# ProPrj_Lan_Relay_blog_2026-03-05_10-33-5.net
KiCad netlist of a schematic drawn in EasyEDA Pro
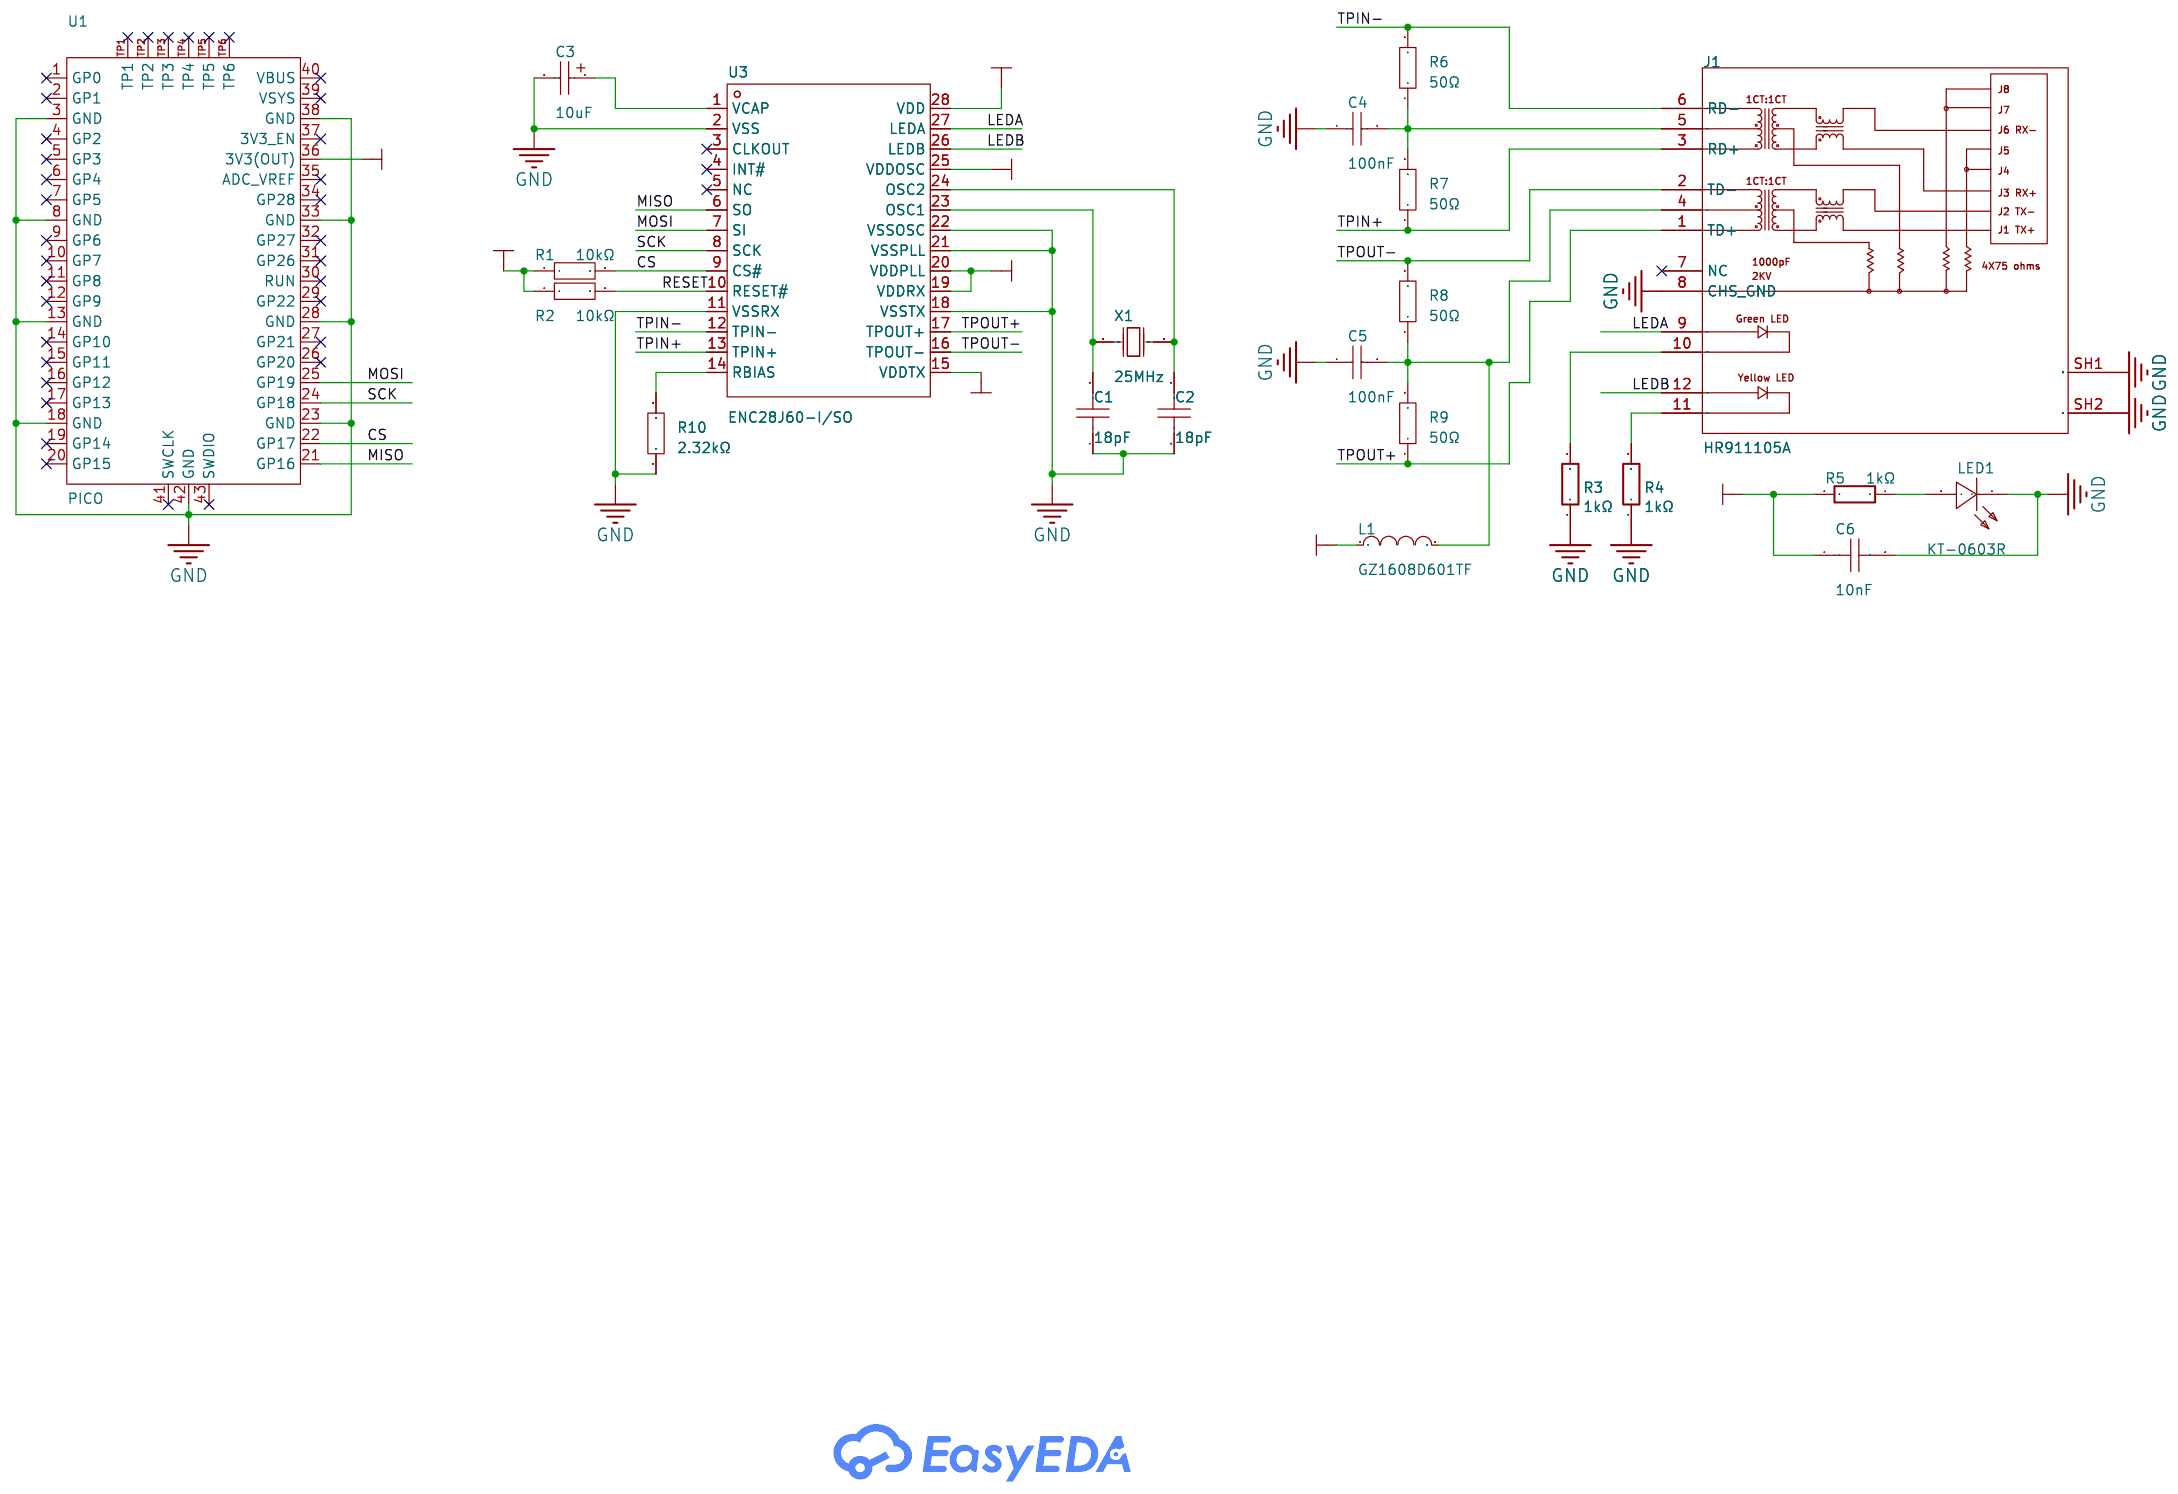
[diagram p0: schematic sheet]

(export (version "E")
  (design (tool "Eeschema 10.0.6"))
  (components
    (comp (ref "C1")
      (value "18pF")
      (description "Capacitance:18pF Tolerance:±5% Tolerance:±5% Voltage Rating:50V Temperature Coefficient:C0G")
      (fields
        (field (name "Manufacturer Part") "CL10C180JB8NNNC")
        (field (name "Manufacturer") "SAMSUNG(三星)")
      )
      (libsource (lib "easyedapro") (part "CAP"))
    )
    (comp (ref "C2")
      (value "18pF")
      (description "Capacitance:18pF Tolerance:±5% Tolerance:±5% Voltage Rating:50V Temperature Coefficient:C0G")
      (fields
        (field (name "Manufacturer Part") "CL10C180JB8NNNC")
        (field (name "Manufacturer") "SAMSUNG(三星)")
      )
      (libsource (lib "easyedapro") (part "CAP"))
    )
    (comp (ref "C3")
      (value "10uF")
      (footprint "easyedapro:CAP-SMD_L3.2-W1.6-RD-C7171")
      (fields (field (name "Manufacturer Part") "TAJA106K016RNJ") (field (name "Manufacturer") "Kyocera AVX"))
      (libsource (lib "easyedapro") (part "TAJA106K016RNJ"))
    )
    (comp (ref "C4")
      (value "100nF")
      (footprint "easyedapro:C0805")
      (description "Capacitance:100nF Tolerance:±10% Tolerance:±10% Voltage Rating:100V Temperature Coefficient:X7R")
      (fields
        (field (name "Manufacturer Part") "CL21B104KCFNNNE")
        (field (name "Manufacturer") "SAMSUNG(三星)")
      )
      (libsource (lib "easyedapro") (part "CL21B104KCFNNNE"))
    )
    (comp (ref "C5")
      (value "100nF")
      (footprint "easyedapro:C0805")
      (description "Capacitance:100nF Tolerance:±10% Tolerance:±10% Voltage Rating:100V Temperature Coefficient:X7R")
      (fields
        (field (name "Manufacturer Part") "CL21B104KCFNNNE")
        (field (name "Manufacturer") "SAMSUNG(三星)")
      )
      (libsource (lib "easyedapro") (part "CL21B104KCFNNNE"))
    )
    (comp (ref "C6")
      (value "10nF")
      (description "Capacitance:10nF Tolerance:±10% Tolerance:±10% Voltage Rating:50V Temperature Coefficient:X7R")
      (fields (field (name "Manufacturer Part") "0603B103K500NT") (field (name "Manufacturer") "FH(风华)"))
      (libsource (lib "easyedapro") (part "CAP"))
    )
    (comp (ref "J1")
      (value "HR911105A")
      (footprint "easyedapro:RJ45-TH_HR911105A")
      (fields (field (name "Manufacturer") "HANRUN(汉仁)"))
      (libsource (lib "easyedapro") (part "HR911105A_C12074"))
    )
    (comp (ref "L1")
      (value "GZ1608D601TF")
      (footprint "easyedapro:L0603")
      (fields (field (name "Manufacturer") "Sunlord(顺络)"))
      (libsource (lib "easyedapro") (part "GZ1608D601TF"))
    )
    (comp (ref "LED1")
      (value "KT-0603R")
      (footprint "easyedapro:LED0603-RD")
      (fields (field (name "Manufacturer") "KENTO"))
      (libsource (lib "easyedapro") (part "KT-0603R"))
    )
    (comp (ref "R1")
      (value "10kΩ")
      (fields
        (field (name "Manufacturer Part") "0603WAF1002T5E")
        (field (name "Manufacturer") "UNI-ROYAL(厚声)")
      )
      (libsource (lib "easyedapro") (part "Res"))
    )
    (comp (ref "R2")
      (value "10kΩ")
      (fields
        (field (name "Manufacturer Part") "0603WAF1002T5E")
        (field (name "Manufacturer") "UNI-ROYAL(厚声)")
      )
      (libsource (lib "easyedapro") (part "Res"))
    )
    (comp (ref "R3")
      (value "1kΩ")
      (fields (field (name "Manufacturer") "UNI-ROYAL(厚声)"))
      (libsource (lib "easyedapro") (part "1k"))
    )
    (comp (ref "R4")
      (value "1kΩ")
      (fields (field (name "Manufacturer") "UNI-ROYAL(厚声)"))
      (libsource (lib "easyedapro") (part "1k"))
    )
    (comp (ref "R5")
      (value "1kΩ")
      (fields (field (name "Manufacturer") "UNI-ROYAL(厚声)"))
      (libsource (lib "easyedapro") (part "1k"))
    )
    (comp (ref "R6")
      (value "50Ω")
      (fields
        (field (name "Manufacturer Part") "CRCW060350R0FKEA")
        (field (name "Manufacturer") "VISHAY(威世)")
      )
      (libsource (lib "easyedapro") (part "Res"))
    )
    (comp (ref "R7")
      (value "50Ω")
      (fields
        (field (name "Manufacturer Part") "CRCW060350R0FKEA")
        (field (name "Manufacturer") "VISHAY(威世)")
      )
      (libsource (lib "easyedapro") (part "Res"))
    )
    (comp (ref "R8")
      (value "50Ω")
      (fields
        (field (name "Manufacturer Part") "CRCW060350R0FKEA")
        (field (name "Manufacturer") "VISHAY(威世)")
      )
      (libsource (lib "easyedapro") (part "Res"))
    )
    (comp (ref "R9")
      (value "50Ω")
      (fields
        (field (name "Manufacturer Part") "CRCW060350R0FKEA")
        (field (name "Manufacturer") "VISHAY(威世)")
      )
      (libsource (lib "easyedapro") (part "Res"))
    )
    (comp (ref "R10")
      (value "2.32kΩ")
      (fields
        (field (name "Manufacturer Part") "0603WAF2321T5E")
        (field (name "Manufacturer") "UNI-ROYAL(厚声)")
      )
      (libsource (lib "easyedapro") (part "Res"))
    )
    (comp (ref "U1")
      (value "PICO")
      (footprint "easyedapro:COMM-SMD_L51.0-W21.0-P2.54_SC0916")
      (fields (field (name "Manufacturer") "Raspberry Pi(树莓派)"))
      (libsource (lib "easyedapro") (part "PICO"))
    )
    (comp (ref "U3")
      (value "ENC28J60-I/SO")
      (footprint "easyedapro:SOIC-28_L17.9-W7.5-P1.27-LS10.3-BL")
      (fields (field (name "Manufacturer") "MICROCHIP(美国微芯)"))
      (libsource (lib "easyedapro") (part "ENC28J60-I/SO"))
    )
    (comp (ref "X1")
      (value "25MHz")
      (footprint "easyedapro:HC-49US_L11.5-W4.5-P4.88")
      (fields (field (name "Manufacturer Part") "X49SD25MSD2SC") (field (name "Manufacturer") "YXC(扬兴晶振)"))
      (libsource (lib "easyedapro") (part "X49SD25MSD2SC"))
    )
  )
  (nets
    (net (code "1") (name "+3.3V") (class "Default")
      (node (ref "C6") (pin "1") (pinfunction "1_1") (pintype "input"))
      (node (ref "L1") (pin "1") (pinfunction "1_1") (pintype "unspecified"))
      (node (ref "R1") (pin "1") (pinfunction "1_1") (pintype "input"))
      (node (ref "R2") (pin "1") (pinfunction "1_1") (pintype "input"))
      (node (ref "R5") (pin "2") (pinfunction "2_2") (pintype "unspecified"))
      (node (ref "U1") (pin "36") (pinfunction "3V3(OUT)_36") (pintype "unspecified"))
      (node (ref "U3") (pin "15") (pinfunction "VDDTX_15") (pintype "unspecified"))
      (node (ref "U3") (pin "19") (pinfunction "VDDRX_19") (pintype "unspecified"))
      (node (ref "U3") (pin "20") (pinfunction "VDDPLL_20") (pintype "unspecified"))
      (node (ref "U3") (pin "25") (pinfunction "VDDOSC_25") (pintype "unspecified"))
      (node (ref "U3") (pin "28") (pinfunction "VDD_28") (pintype "unspecified"))
    )
    (net (code "2") (name "/CS") (class "Default")
      (node (ref "R1") (pin "2") (pinfunction "2_2") (pintype "input"))
      (node (ref "U1") (pin "22") (pinfunction "GP17_22") (pintype "unspecified"))
      (node (ref "U3") (pin "9") (pinfunction "CS#_9") (pintype "unspecified"))
    )
    (net (code "3") (name "/LEDA") (class "Default")
      (node (ref "J1") (pin "9") (pinfunction "9_9") (pintype "unspecified"))
      (node (ref "U3") (pin "27") (pinfunction "LEDA_27") (pintype "unspecified"))
    )
    (net (code "4") (name "/LEDB") (class "Default")
      (node (ref "J1") (pin "12") (pinfunction "12_12") (pintype "unspecified"))
      (node (ref "U3") (pin "26") (pinfunction "LEDB_26") (pintype "unspecified"))
    )
    (net (code "5") (name "/MISO") (class "Default")
      (node (ref "U1") (pin "21") (pinfunction "GP16_21") (pintype "unspecified"))
      (node (ref "U3") (pin "6") (pinfunction "SO_6") (pintype "unspecified"))
    )
    (net (code "6") (name "/MOSI") (class "Default")
      (node (ref "U1") (pin "25") (pinfunction "GP19_25") (pintype "unspecified"))
      (node (ref "U3") (pin "7") (pinfunction "SI_7") (pintype "unspecified"))
    )
    (net (code "7") (name "/RESET") (class "Default")
      (node (ref "R2") (pin "2") (pinfunction "2_2") (pintype "input"))
      (node (ref "U3") (pin "10") (pinfunction "RESET#_10") (pintype "unspecified"))
    )
    (net (code "8") (name "/SCK") (class "Default")
      (node (ref "U1") (pin "24") (pinfunction "GP18_24") (pintype "unspecified"))
      (node (ref "U3") (pin "8") (pinfunction "SCK_8") (pintype "unspecified"))
    )
    (net (code "9") (name "/TPIN+") (class "Default")
      (node (ref "J1") (pin "3") (pinfunction "RD+_3") (pintype "unspecified"))
      (node (ref "R7") (pin "1") (pinfunction "1_1") (pintype "input"))
      (node (ref "U3") (pin "13") (pinfunction "TPIN+_13") (pintype "unspecified"))
    )
    (net (code "10") (name "/TPIN-") (class "Default")
      (node (ref "J1") (pin "6") (pinfunction "RD-_6") (pintype "unspecified"))
      (node (ref "R6") (pin "2") (pinfunction "2_2") (pintype "input"))
      (node (ref "U3") (pin "12") (pinfunction "TPIN-_12") (pintype "unspecified"))
    )
    (net (code "11") (name "/TPOUT+") (class "Default")
      (node (ref "J1") (pin "1") (pinfunction "TD+_1") (pintype "unspecified"))
      (node (ref "R9") (pin "1") (pinfunction "1_1") (pintype "input"))
      (node (ref "U3") (pin "17") (pinfunction "TPOUT+_17") (pintype "unspecified"))
    )
    (net (code "12") (name "/TPOUT-") (class "Default")
      (node (ref "J1") (pin "2") (pinfunction "TD-_2") (pintype "unspecified"))
      (node (ref "R8") (pin "2") (pinfunction "2_2") (pintype "input"))
      (node (ref "U3") (pin "16") (pinfunction "TPOUT-_16") (pintype "unspecified"))
    )
    (net (code "13") (name "GND") (class "Default")
      (node (ref "C1") (pin "1") (pinfunction "1_1") (pintype "input"))
      (node (ref "C2") (pin "1") (pinfunction "1_1") (pintype "input"))
      (node (ref "C3") (pin "2") (pinfunction "2_2") (pintype "input"))
      (node (ref "C4") (pin "1") (pinfunction "1_1") (pintype "input"))
      (node (ref "C5") (pin "1") (pinfunction "1_1") (pintype "input"))
      (node (ref "C6") (pin "2") (pinfunction "2_2") (pintype "input"))
      (node (ref "J1") (pin "8") (pinfunction "CHS_GND_8") (pintype "unspecified"))
      (node (ref "J1") (pin "SH1") (pinfunction "SH1_SH1") (pintype "unspecified"))
      (node (ref "J1") (pin "SH2") (pinfunction "SH2_SH2") (pintype "unspecified"))
      (node (ref "LED1") (pin "1") (pinfunction "K_1") (pintype "unspecified"))
      (node (ref "R10") (pin "1") (pinfunction "1_1") (pintype "input"))
      (node (ref "R3") (pin "1") (pinfunction "1_1") (pintype "unspecified"))
      (node (ref "R4") (pin "1") (pinfunction "1_1") (pintype "unspecified"))
      (node (ref "U1") (pin "13") (pinfunction "GND_13") (pintype "unspecified"))
      (node (ref "U1") (pin "18") (pinfunction "GND_18") (pintype "unspecified"))
      (node (ref "U1") (pin "23") (pinfunction "GND_23") (pintype "unspecified"))
      (node (ref "U1") (pin "28") (pinfunction "GND_28") (pintype "unspecified"))
      (node (ref "U1") (pin "3") (pinfunction "GND_3") (pintype "unspecified"))
      (node (ref "U1") (pin "33") (pinfunction "GND_33") (pintype "unspecified"))
      (node (ref "U1") (pin "38") (pinfunction "GND_38") (pintype "unspecified"))
      (node (ref "U1") (pin "42") (pinfunction "GND_42") (pintype "unspecified"))
      (node (ref "U1") (pin "8") (pinfunction "GND_8") (pintype "unspecified"))
      (node (ref "U3") (pin "11") (pinfunction "VSSRX_11") (pintype "unspecified"))
      (node (ref "U3") (pin "18") (pinfunction "VSSTX_18") (pintype "unspecified"))
      (node (ref "U3") (pin "2") (pinfunction "VSS_2") (pintype "unspecified"))
      (node (ref "U3") (pin "21") (pinfunction "VSSPLL_21") (pintype "unspecified"))
      (node (ref "U3") (pin "22") (pinfunction "VSSOSC_22") (pintype "unspecified"))
    )
    (net (code "14") (name "Net-(C4-Pad2)") (class "Default")
      (node (ref "C4") (pin "2") (pinfunction "2_2") (pintype "input"))
      (node (ref "J1") (pin "5") (pinfunction "5_5") (pintype "unspecified"))
      (node (ref "R6") (pin "1") (pinfunction "1_1") (pintype "input"))
      (node (ref "R7") (pin "2") (pinfunction "2_2") (pintype "input"))
    )
    (net (code "15") (name "Net-(C5-Pad2)") (class "Default")
      (node (ref "C5") (pin "2") (pinfunction "2_2") (pintype "input"))
      (node (ref "J1") (pin "4") (pinfunction "4_4") (pintype "unspecified"))
      (node (ref "L1") (pin "2") (pinfunction "2_2") (pintype "unspecified"))
      (node (ref "R8") (pin "1") (pinfunction "1_1") (pintype "input"))
      (node (ref "R9") (pin "2") (pinfunction "2_2") (pintype "input"))
    )
    (net (code "16") (name "Net-(J1-Pad10)") (class "Default")
      (node (ref "J1") (pin "10") (pinfunction "10_10") (pintype "unspecified"))
      (node (ref "R3") (pin "2") (pinfunction "2_2") (pintype "unspecified"))
    )
    (net (code "17") (name "Net-(J1-Pad11)") (class "Default")
      (node (ref "J1") (pin "11") (pinfunction "11_11") (pintype "unspecified"))
      (node (ref "R4") (pin "2") (pinfunction "2_2") (pintype "unspecified"))
    )
    (net (code "18") (name "Net-(LED1-A)") (class "Default")
      (node (ref "LED1") (pin "2") (pinfunction "A_2") (pintype "unspecified"))
      (node (ref "R5") (pin "1") (pinfunction "1_1") (pintype "unspecified"))
    )
    (net (code "19") (name "Net-(U3-OSC1)") (class "Default")
      (node (ref "C1") (pin "2") (pinfunction "2_2") (pintype "input"))
      (node (ref "U3") (pin "23") (pinfunction "OSC1_23") (pintype "unspecified"))
      (node (ref "X1") (pin "2") (pinfunction "OSC2_2") (pintype "input"))
    )
    (net (code "20") (name "Net-(U3-OSC2)") (class "Default")
      (node (ref "C2") (pin "2") (pinfunction "2_2") (pintype "input"))
      (node (ref "U3") (pin "24") (pinfunction "OSC2_24") (pintype "unspecified"))
      (node (ref "X1") (pin "1") (pinfunction "OSC1_1") (pintype "input"))
    )
    (net (code "21") (name "Net-(U3-RBIAS)") (class "Default")
      (node (ref "R10") (pin "2") (pinfunction "2_2") (pintype "input"))
      (node (ref "U3") (pin "14") (pinfunction "RBIAS_14") (pintype "unspecified"))
    )
    (net (code "22") (name "Net-(U3-VCAP)") (class "Default")
      (node (ref "C3") (pin "1") (pinfunction "1_1") (pintype "input"))
      (node (ref "U3") (pin "1") (pinfunction "VCAP_1") (pintype "unspecified"))
    )
    (net (code "23") (name "unconnected-(J1-NC-Pad7)") (class "Default")
      (node (ref "J1") (pin "7") (pinfunction "NC_7") (pintype "unspecified+no_connect"))
    )
    (net (code "24") (name "unconnected-(U1-3V3_EN-Pad37)") (class "Default")
      (node (ref "U1") (pin "37") (pinfunction "3V3_EN_37") (pintype "unspecified+no_connect"))
    )
    (net (code "25") (name "unconnected-(U1-ADC_VREF-Pad35)") (class "Default")
      (node (ref "U1") (pin "35") (pinfunction "ADC_VREF_35") (pintype "unspecified+no_connect"))
    )
    (net (code "26") (name "unconnected-(U1-GP0-Pad1)") (class "Default")
      (node (ref "U1") (pin "1") (pinfunction "GP0_1") (pintype "unspecified+no_connect"))
    )
    (net (code "27") (name "unconnected-(U1-GP1-Pad2)") (class "Default")
      (node (ref "U1") (pin "2") (pinfunction "GP1_2") (pintype "unspecified+no_connect"))
    )
    (net (code "28") (name "unconnected-(U1-GP2-Pad4)") (class "Default")
      (node (ref "U1") (pin "4") (pinfunction "GP2_4") (pintype "unspecified+no_connect"))
    )
    (net (code "29") (name "unconnected-(U1-GP3-Pad5)") (class "Default")
      (node (ref "U1") (pin "5") (pinfunction "GP3_5") (pintype "unspecified+no_connect"))
    )
    (net (code "30") (name "unconnected-(U1-GP4-Pad6)") (class "Default")
      (node (ref "U1") (pin "6") (pinfunction "GP4_6") (pintype "unspecified+no_connect"))
    )
    (net (code "31") (name "unconnected-(U1-GP5-Pad7)") (class "Default")
      (node (ref "U1") (pin "7") (pinfunction "GP5_7") (pintype "unspecified+no_connect"))
    )
    (net (code "32") (name "unconnected-(U1-GP6-Pad9)") (class "Default")
      (node (ref "U1") (pin "9") (pinfunction "GP6_9") (pintype "unspecified+no_connect"))
    )
    (net (code "33") (name "unconnected-(U1-GP7-Pad10)") (class "Default")
      (node (ref "U1") (pin "10") (pinfunction "GP7_10") (pintype "unspecified+no_connect"))
    )
    (net (code "34") (name "unconnected-(U1-GP8-Pad11)") (class "Default")
      (node (ref "U1") (pin "11") (pinfunction "GP8_11") (pintype "unspecified+no_connect"))
    )
    (net (code "35") (name "unconnected-(U1-GP9-Pad12)") (class "Default")
      (node (ref "U1") (pin "12") (pinfunction "GP9_12") (pintype "unspecified+no_connect"))
    )
    (net (code "36") (name "unconnected-(U1-GP10-Pad14)") (class "Default")
      (node (ref "U1") (pin "14") (pinfunction "GP10_14") (pintype "unspecified+no_connect"))
    )
    (net (code "37") (name "unconnected-(U1-GP11-Pad15)") (class "Default")
      (node (ref "U1") (pin "15") (pinfunction "GP11_15") (pintype "unspecified+no_connect"))
    )
    (net (code "38") (name "unconnected-(U1-GP12-Pad16)") (class "Default")
      (node (ref "U1") (pin "16") (pinfunction "GP12_16") (pintype "unspecified+no_connect"))
    )
    (net (code "39") (name "unconnected-(U1-GP13-Pad17)") (class "Default")
      (node (ref "U1") (pin "17") (pinfunction "GP13_17") (pintype "unspecified+no_connect"))
    )
    (net (code "40") (name "unconnected-(U1-GP14-Pad19)") (class "Default")
      (node (ref "U1") (pin "19") (pinfunction "GP14_19") (pintype "unspecified+no_connect"))
    )
    (net (code "41") (name "unconnected-(U1-GP15-Pad20)") (class "Default")
      (node (ref "U1") (pin "20") (pinfunction "GP15_20") (pintype "unspecified+no_connect"))
    )
    (net (code "42") (name "unconnected-(U1-GP20-Pad26)") (class "Default")
      (node (ref "U1") (pin "26") (pinfunction "GP20_26") (pintype "unspecified+no_connect"))
    )
    (net (code "43") (name "unconnected-(U1-GP21-Pad27)") (class "Default")
      (node (ref "U1") (pin "27") (pinfunction "GP21_27") (pintype "unspecified+no_connect"))
    )
    (net (code "44") (name "unconnected-(U1-GP22-Pad29)") (class "Default")
      (node (ref "U1") (pin "29") (pinfunction "GP22_29") (pintype "unspecified+no_connect"))
    )
    (net (code "45") (name "unconnected-(U1-GP26-Pad31)") (class "Default")
      (node (ref "U1") (pin "31") (pinfunction "GP26_31") (pintype "unspecified+no_connect"))
    )
    (net (code "46") (name "unconnected-(U1-GP27-Pad32)") (class "Default")
      (node (ref "U1") (pin "32") (pinfunction "GP27_32") (pintype "unspecified+no_connect"))
    )
    (net (code "47") (name "unconnected-(U1-GP28-Pad34)") (class "Default")
      (node (ref "U1") (pin "34") (pinfunction "GP28_34") (pintype "unspecified+no_connect"))
    )
    (net (code "48") (name "unconnected-(U1-PadTP1)") (class "Default")
      (node (ref "U1") (pin "TP1") (pinfunction "TP1_TP1") (pintype "unspecified+no_connect"))
    )
    (net (code "49") (name "unconnected-(U1-PadTP2)") (class "Default")
      (node (ref "U1") (pin "TP2") (pinfunction "TP2_TP2") (pintype "unspecified+no_connect"))
    )
    (net (code "50") (name "unconnected-(U1-PadTP3)") (class "Default")
      (node (ref "U1") (pin "TP3") (pinfunction "TP3_TP3") (pintype "unspecified+no_connect"))
    )
    (net (code "51") (name "unconnected-(U1-PadTP4)") (class "Default")
      (node (ref "U1") (pin "TP4") (pinfunction "TP4_TP4") (pintype "unspecified+no_connect"))
    )
    (net (code "52") (name "unconnected-(U1-PadTP5)") (class "Default")
      (node (ref "U1") (pin "TP5") (pinfunction "TP5_TP5") (pintype "unspecified+no_connect"))
    )
    (net (code "53") (name "unconnected-(U1-PadTP6)") (class "Default")
      (node (ref "U1") (pin "TP6") (pinfunction "TP6_TP6") (pintype "unspecified+no_connect"))
    )
    (net (code "54") (name "unconnected-(U1-RUN-Pad30)") (class "Default")
      (node (ref "U1") (pin "30") (pinfunction "RUN_30") (pintype "unspecified+no_connect"))
    )
    (net (code "55") (name "unconnected-(U1-SWCLK-Pad41)") (class "Default")
      (node (ref "U1") (pin "41") (pinfunction "SWCLK_41") (pintype "unspecified+no_connect"))
    )
    (net (code "56") (name "unconnected-(U1-SWDIO-Pad43)") (class "Default")
      (node (ref "U1") (pin "43") (pinfunction "SWDIO_43") (pintype "unspecified+no_connect"))
    )
    (net (code "57") (name "unconnected-(U1-VBUS-Pad40)") (class "Default")
      (node (ref "U1") (pin "40") (pinfunction "VBUS_40") (pintype "unspecified+no_connect"))
    )
    (net (code "58") (name "unconnected-(U1-VSYS-Pad39)") (class "Default")
      (node (ref "U1") (pin "39") (pinfunction "VSYS_39") (pintype "unspecified+no_connect"))
    )
    (net (code "59") (name "unconnected-(U3-CLKOUT-Pad3)") (class "Default")
      (node (ref "U3") (pin "3") (pinfunction "CLKOUT_3") (pintype "unspecified+no_connect"))
    )
    (net (code "60") (name "unconnected-(U3-INT#-Pad4)") (class "Default")
      (node (ref "U3") (pin "4") (pinfunction "INT#_4") (pintype "unspecified+no_connect"))
    )
    (net (code "61") (name "unconnected-(U3-NC-Pad5)") (class "Default")
      (node (ref "U3") (pin "5") (pinfunction "NC_5") (pintype "unspecified+no_connect"))
    )
  )
)
